# p1-001.net
KiCad netlist of a schematic drawn in EAGLE
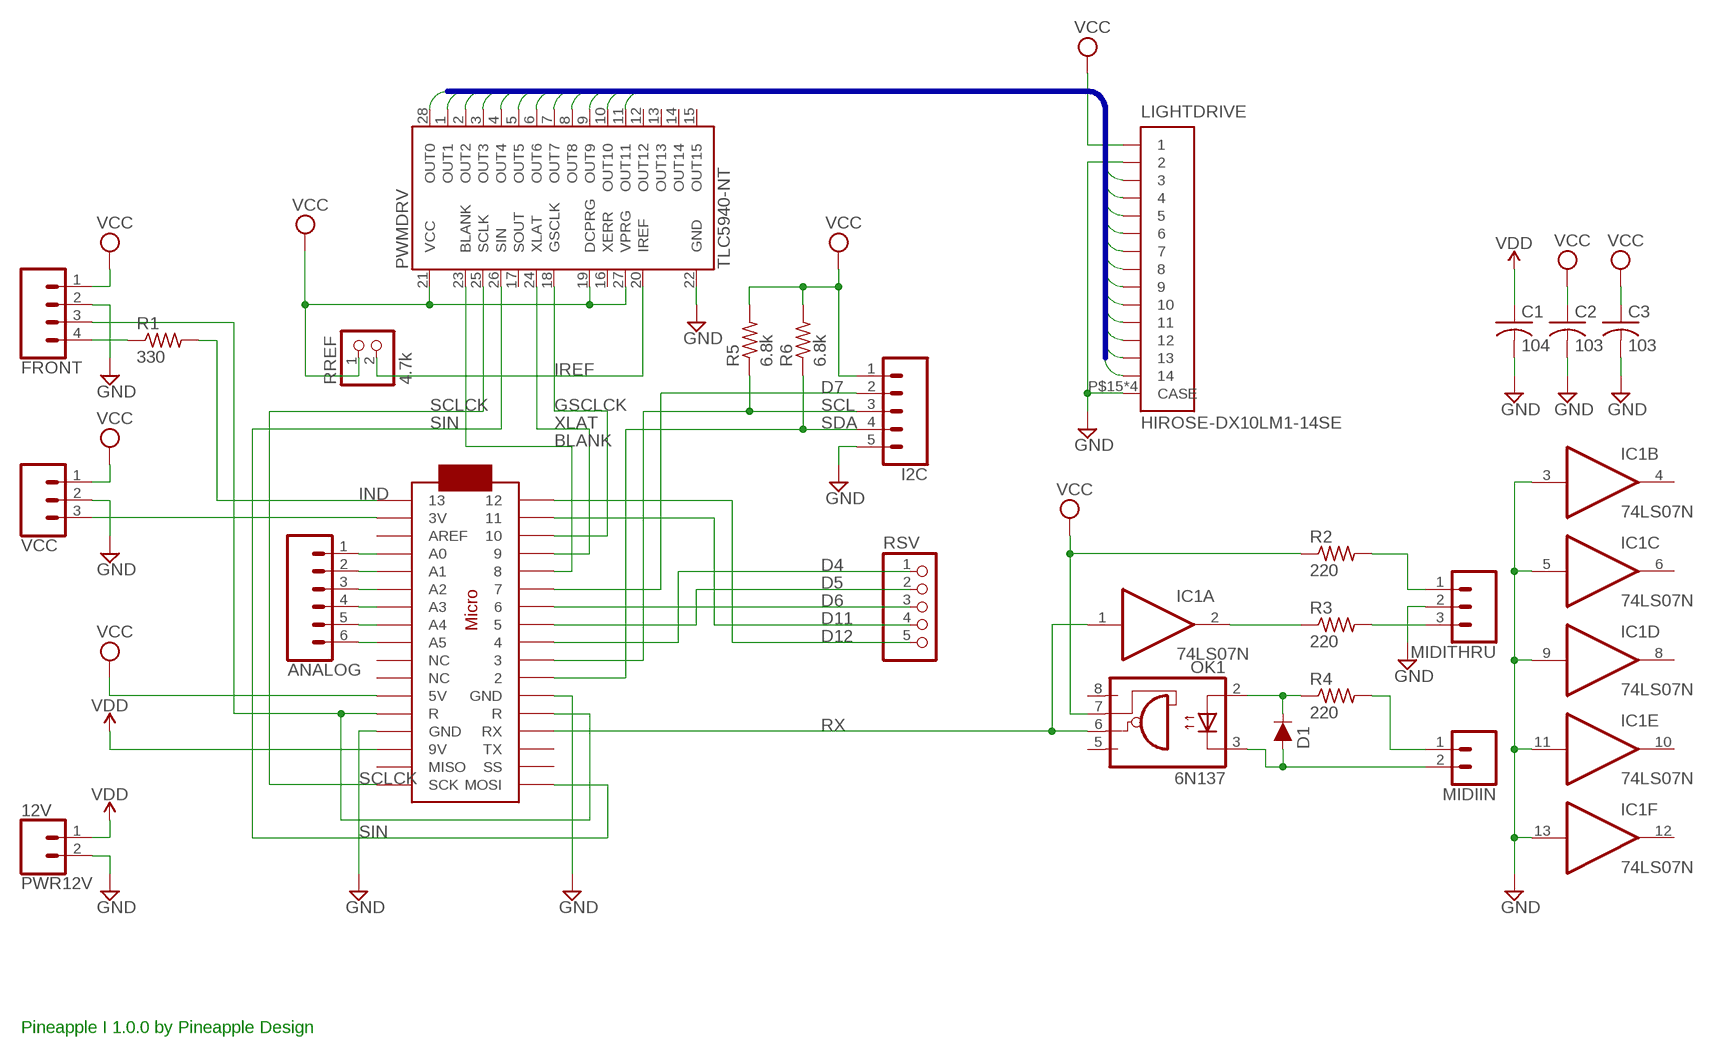
[diagram p0: schematic, sheet 1]

(export (version "E")
  (design (tool "Eeschema 10.0.6"))
  (components
    (comp (ref "ANALOG")
      (value "CONN_061.27MM")
      (footprint "eagle-import:1X06_1.27MM")
      (libsource (lib "eagle-import") (part "CONN_061.27MM"))
    )
    (comp (ref "C1")
      (value "104")
      (footprint "eagle-import:C025-025X050")
      (libsource (lib "eagle-import") (part "C-US025-025X050"))
    )
    (comp (ref "C2")
      (value "103")
      (footprint "eagle-import:C025-025X050")
      (libsource (lib "eagle-import") (part "C-US025-025X050"))
    )
    (comp (ref "C3")
      (value "103")
      (footprint "eagle-import:C025-025X050")
      (libsource (lib "eagle-import") (part "C-US025-025X050"))
    )
    (comp (ref "D1")
      (value "DIODE-1N4148")
      (footprint "eagle-import:DIODE-1N4148")
      (libsource (lib "eagle-import") (part "DIODE-1N4148"))
    )
    (comp (ref "FRONT")
      (value "CONN_04JST-PTH")
      (footprint "eagle-import:JST-4-PTH")
      (libsource (lib "eagle-import") (part "CONN_04JST-PTH"))
    )
    (comp (ref "I2C")
      (value "CONN_05SMD2")
      (footprint "eagle-import:1X05_1MM_RA")
      (libsource (lib "eagle-import") (part "CONN_05SMD2"))
    )
    (comp (ref "IC1")
      (value "74LS07N")
      (footprint "eagle-import:DIL14")
      (libsource (lib "eagle-import") (part "7407NLS"))
    )
    (comp (ref "LIGHTDRIVE")
      (value "HIROSE-DX10LM1-14SE")
      (footprint "eagle-import:HIROSE-DX10LM1-14SE")
      (fields (field (name "MPN") "AXR30545"))
      (libsource (lib "eagle-import") (part "HIROSE-DX10LM1-14SE"))
    )
    (comp (ref "MIDIIN")
      (value "CONN_02JST-PTH-2")
      (footprint "eagle-import:JST-2-PTH")
      (libsource (lib "eagle-import") (part "CONN_02JST-PTH-2"))
    )
    (comp (ref "MIDITHRU")
      (value "CONN_03JST-PTH")
      (footprint "eagle-import:JST-3-PTH")
      (libsource (lib "eagle-import") (part "CONN_03JST-PTH"))
    )
    (comp (ref "OK1")
      (value "6N137")
      (footprint "eagle-import:DIL08")
      (libsource (lib "eagle-import") (part "6N137"))
    )
    (comp (ref "PWMDRV")
      (value "TLC5940-NT")
      (footprint "eagle-import:DIL28-3")
      (libsource (lib "eagle-import") (part "TLC5940-NT"))
    )
    (comp (ref "PWR12V")
      (value "12V")
      (footprint "eagle-import:JST-2-PTH")
      (libsource (lib "eagle-import") (part "CONN_02JST-PTH-2"))
    )
    (comp (ref "R1")
      (value "330")
      (footprint "eagle-import:0204_5")
      (libsource (lib "eagle-import") (part "R-US_0204/5"))
    )
    (comp (ref "R2")
      (value "220")
      (footprint "eagle-import:0204_5")
      (libsource (lib "eagle-import") (part "R-US_0204/5"))
    )
    (comp (ref "R3")
      (value "220")
      (footprint "eagle-import:0204_5")
      (libsource (lib "eagle-import") (part "R-US_0204/5"))
    )
    (comp (ref "R4")
      (value "220")
      (footprint "eagle-import:0204_5")
      (libsource (lib "eagle-import") (part "R-US_0204/5"))
    )
    (comp (ref "R5")
      (value "6.8k")
      (footprint "eagle-import:0204_5")
      (libsource (lib "eagle-import") (part "R-US_0204/5"))
    )
    (comp (ref "R6")
      (value "6.8k")
      (footprint "eagle-import:0204_5")
      (libsource (lib "eagle-import") (part "R-US_0204/5"))
    )
    (comp (ref "RREF")
      (value "4.7k")
      (footprint "eagle-import:1X02")
      (libsource (lib "eagle-import") (part "PINHD-1X2"))
    )
    (comp (ref "RSV")
      (value "PINHD-1X5")
      (footprint "eagle-import:1X05")
      (libsource (lib "eagle-import") (part "PINHD-1X5"))
    )
    (comp (ref "U$1")
      (value "ARDUINOMICRO")
      (footprint "eagle-import:ARDUINOMICRO")
      (libsource (lib "eagle-import") (part "ARDUINOMICRO"))
    )
    (comp (ref "VCC")
      (value "CONN_03JST-PTH")
      (footprint "eagle-import:JST-3-PTH")
      (libsource (lib "eagle-import") (part "SparkFun-Connectors_513_CONN_03JST-PTH"))
    )
  )
  (nets
    (net (code "1") (name "/BLANK") (class "Default")
      (node (ref "PWMDRV") (pin "23") (pinfunction "BLANK_23") (pintype "bidirectional"))
      (node (ref "U$1") (pin "P$5") (pinfunction "8_P$5") (pintype "bidirectional"))
    )
    (net (code "2") (name "/D4") (class "Default")
      (node (ref "RSV") (pin "1") (pinfunction "1_1") (pintype "passive"))
      (node (ref "U$1") (pin "P$9") (pinfunction "4_P$9") (pintype "bidirectional"))
    )
    (net (code "3") (name "/D5") (class "Default")
      (node (ref "RSV") (pin "2") (pinfunction "2_2") (pintype "passive"))
      (node (ref "U$1") (pin "P$8") (pinfunction "5_P$8") (pintype "bidirectional"))
    )
    (net (code "4") (name "/D6") (class "Default")
      (node (ref "RSV") (pin "3") (pinfunction "3_3") (pintype "passive"))
      (node (ref "U$1") (pin "P$7") (pinfunction "6_P$7") (pintype "bidirectional"))
    )
    (net (code "5") (name "/D7") (class "Default")
      (node (ref "I2C") (pin "2") (pinfunction "2_2") (pintype "passive"))
      (node (ref "U$1") (pin "P$6") (pinfunction "7_P$6") (pintype "bidirectional"))
    )
    (net (code "6") (name "/D11") (class "Default")
      (node (ref "RSV") (pin "4") (pinfunction "4_4") (pintype "passive"))
      (node (ref "U$1") (pin "P$2") (pinfunction "11_P$2") (pintype "bidirectional"))
    )
    (net (code "7") (name "/D12") (class "Default")
      (node (ref "RSV") (pin "5") (pinfunction "5_5") (pintype "passive"))
      (node (ref "U$1") (pin "P$1") (pinfunction "12_P$1") (pintype "bidirectional"))
    )
    (net (code "8") (name "/GSCLCK") (class "Default")
      (node (ref "PWMDRV") (pin "18") (pinfunction "GSCLK_18") (pintype "bidirectional"))
      (node (ref "U$1") (pin "P$3") (pinfunction "10_P$3") (pintype "bidirectional"))
    )
    (net (code "9") (name "/IND") (class "Default")
      (node (ref "R1") (pin "2") (pinfunction "2_2") (pintype "passive"))
      (node (ref "U$1") (pin "P$34") (pinfunction "13_P$34") (pintype "bidirectional"))
    )
    (net (code "10") (name "/IREF") (class "Default")
      (node (ref "PWMDRV") (pin "20") (pinfunction "IREF_20") (pintype "bidirectional"))
      (node (ref "RREF") (pin "2") (pinfunction "2_2") (pintype "passive"))
    )
    (net (code "11") (name "/LD1") (class "Default")
      (node (ref "LIGHTDRIVE") (pin "P$3") (pinfunction "3_P$3") (pintype "bidirectional"))
      (node (ref "PWMDRV") (pin "28") (pinfunction "OUT0_28") (pintype "bidirectional"))
    )
    (net (code "12") (name "/LD2") (class "Default")
      (node (ref "LIGHTDRIVE") (pin "P$4") (pinfunction "4_P$4") (pintype "bidirectional"))
      (node (ref "PWMDRV") (pin "1") (pinfunction "OUT1_1") (pintype "bidirectional"))
    )
    (net (code "13") (name "/LD3") (class "Default")
      (node (ref "LIGHTDRIVE") (pin "P$5") (pinfunction "5_P$5") (pintype "bidirectional"))
      (node (ref "PWMDRV") (pin "2") (pinfunction "OUT2_2") (pintype "bidirectional"))
    )
    (net (code "14") (name "/LD4") (class "Default")
      (node (ref "LIGHTDRIVE") (pin "P$6") (pinfunction "6_P$6") (pintype "bidirectional"))
      (node (ref "PWMDRV") (pin "3") (pinfunction "OUT3_3") (pintype "bidirectional"))
    )
    (net (code "15") (name "/LD5") (class "Default")
      (node (ref "LIGHTDRIVE") (pin "P$7") (pinfunction "7_P$7") (pintype "bidirectional"))
      (node (ref "PWMDRV") (pin "4") (pinfunction "OUT4_4") (pintype "bidirectional"))
    )
    (net (code "16") (name "/LD6") (class "Default")
      (node (ref "LIGHTDRIVE") (pin "P$8") (pinfunction "8_P$8") (pintype "bidirectional"))
      (node (ref "PWMDRV") (pin "5") (pinfunction "OUT5_5") (pintype "bidirectional"))
    )
    (net (code "17") (name "/LD7") (class "Default")
      (node (ref "LIGHTDRIVE") (pin "P$9") (pinfunction "9_P$9") (pintype "bidirectional"))
      (node (ref "PWMDRV") (pin "6") (pinfunction "OUT6_6") (pintype "bidirectional"))
    )
    (net (code "18") (name "/LD8") (class "Default")
      (node (ref "LIGHTDRIVE") (pin "P$10") (pinfunction "10_P$10") (pintype "bidirectional"))
      (node (ref "PWMDRV") (pin "7") (pinfunction "OUT7_7") (pintype "bidirectional"))
    )
    (net (code "19") (name "/LD9") (class "Default")
      (node (ref "LIGHTDRIVE") (pin "P$11") (pinfunction "11_P$11") (pintype "bidirectional"))
      (node (ref "PWMDRV") (pin "8") (pinfunction "OUT8_8") (pintype "bidirectional"))
    )
    (net (code "20") (name "/LD10") (class "Default")
      (node (ref "LIGHTDRIVE") (pin "P$12") (pinfunction "12_P$12") (pintype "bidirectional"))
      (node (ref "PWMDRV") (pin "9") (pinfunction "OUT9_9") (pintype "bidirectional"))
    )
    (net (code "21") (name "/LD11") (class "Default")
      (node (ref "LIGHTDRIVE") (pin "P$13") (pinfunction "13_P$13") (pintype "bidirectional"))
      (node (ref "PWMDRV") (pin "10") (pinfunction "OUT10_10") (pintype "bidirectional"))
    )
    (net (code "22") (name "/LD12") (class "Default")
      (node (ref "LIGHTDRIVE") (pin "P$14") (pinfunction "14_P$14") (pintype "bidirectional"))
      (node (ref "PWMDRV") (pin "11") (pinfunction "OUT11_11") (pintype "bidirectional"))
    )
    (net (code "23") (name "/RX") (class "Default")
      (node (ref "IC1") (pin "1") (pinfunction "I_1") (pintype "input"))
      (node (ref "OK1") (pin "6") (pinfunction "VO_6") (pintype "passive"))
      (node (ref "U$1") (pin "P$14") (pinfunction "RX_P$14") (pintype "bidirectional"))
    )
    (net (code "24") (name "/SCL") (class "Default")
      (node (ref "I2C") (pin "3") (pinfunction "3_3") (pintype "passive"))
      (node (ref "R5") (pin "1") (pinfunction "1_1") (pintype "passive"))
      (node (ref "U$1") (pin "P$10") (pinfunction "3_P$10") (pintype "bidirectional"))
    )
    (net (code "25") (name "/SCLCK") (class "Default")
      (node (ref "PWMDRV") (pin "25") (pinfunction "SCLK_25") (pintype "bidirectional"))
      (node (ref "U$1") (pin "P$18") (pinfunction "SCK_P$18") (pintype "bidirectional"))
    )
    (net (code "26") (name "/SDA") (class "Default")
      (node (ref "I2C") (pin "4") (pinfunction "4_4") (pintype "passive"))
      (node (ref "R6") (pin "1") (pinfunction "1_1") (pintype "passive"))
      (node (ref "U$1") (pin "P$11") (pinfunction "2_P$11") (pintype "bidirectional"))
    )
    (net (code "27") (name "/SIN") (class "Default")
      (node (ref "PWMDRV") (pin "26") (pinfunction "SIN_26") (pintype "bidirectional"))
      (node (ref "U$1") (pin "P$17") (pinfunction "MOSI_P$17") (pintype "bidirectional"))
    )
    (net (code "28") (name "/XLAT") (class "Default")
      (node (ref "PWMDRV") (pin "24") (pinfunction "XLAT_24") (pintype "bidirectional"))
      (node (ref "U$1") (pin "P$4") (pinfunction "9_P$4") (pintype "bidirectional"))
    )
    (net (code "29") (name "GND") (class "Default")
      (node (ref "C1") (pin "2") (pinfunction "2_2") (pintype "passive"))
      (node (ref "C2") (pin "2") (pinfunction "2_2") (pintype "passive"))
      (node (ref "C3") (pin "2") (pinfunction "2_2") (pintype "passive"))
      (node (ref "FRONT") (pin "2") (pinfunction "2_2") (pintype "passive"))
      (node (ref "I2C") (pin "5") (pinfunction "5_5") (pintype "passive"))
      (node (ref "IC1") (pin "11") (pinfunction "I_11") (pintype "input"))
      (node (ref "IC1") (pin "13") (pinfunction "I_13") (pintype "input"))
      (node (ref "IC1") (pin "3") (pinfunction "I_3") (pintype "input"))
      (node (ref "IC1") (pin "5") (pinfunction "I_5") (pintype "input"))
      (node (ref "IC1") (pin "9") (pinfunction "I_9") (pintype "input"))
      (node (ref "LIGHTDRIVE") (pin "P$15") (pinfunction "CASE_P$15") (pintype "bidirectional"))
      (node (ref "LIGHTDRIVE") (pin "P$16") (pinfunction "CASE_P$16") (pintype "bidirectional"))
      (node (ref "LIGHTDRIVE") (pin "P$17") (pinfunction "CASE_P$17") (pintype "bidirectional"))
      (node (ref "LIGHTDRIVE") (pin "P$18") (pinfunction "CASE_P$18") (pintype "bidirectional"))
      (node (ref "LIGHTDRIVE") (pin "P$2") (pinfunction "2_P$2") (pintype "bidirectional"))
      (node (ref "MIDITHRU") (pin "2") (pinfunction "2_2") (pintype "passive"))
      (node (ref "PWMDRV") (pin "22") (pinfunction "GND_22") (pintype "bidirectional"))
      (node (ref "PWR12V") (pin "2") (pinfunction "2_2") (pintype "passive"))
      (node (ref "U$1") (pin "P$12") (pinfunction "GND_P$12") (pintype "bidirectional"))
      (node (ref "U$1") (pin "P$21") (pinfunction "GND_P$21") (pintype "bidirectional"))
      (node (ref "VCC") (pin "2") (pinfunction "2_2") (pintype "passive"))
    )
    (net (code "30") (name "Net-(FRONT-Pad3)") (class "Default")
      (node (ref "FRONT") (pin "3") (pinfunction "3_3") (pintype "passive"))
      (node (ref "U$1") (pin "P$13") (pinfunction "R_P$13") (pintype "bidirectional"))
      (node (ref "U$1") (pin "P$22") (pinfunction "R_P$22") (pintype "bidirectional"))
    )
    (net (code "31") (name "Net-(FRONT-Pad4)") (class "Default")
      (node (ref "FRONT") (pin "4") (pinfunction "4_4") (pintype "passive"))
      (node (ref "R1") (pin "1") (pinfunction "1_1") (pintype "passive"))
    )
    (net (code "32") (name "Net-(IC1A-O)") (class "Default")
      (node (ref "IC1") (pin "2") (pinfunction "O_2") (pintype "open_collector"))
      (node (ref "R3") (pin "1") (pinfunction "1_1") (pintype "passive"))
    )
    (net (code "33") (name "Net-(MIDIIN-Pad1)") (class "Default")
      (node (ref "MIDIIN") (pin "1") (pinfunction "1_1") (pintype "passive"))
      (node (ref "R4") (pin "2") (pinfunction "2_2") (pintype "passive"))
    )
    (net (code "34") (name "Net-(MIDITHRU-Pad1)") (class "Default")
      (node (ref "MIDITHRU") (pin "1") (pinfunction "1_1") (pintype "passive"))
      (node (ref "R2") (pin "2") (pinfunction "2_2") (pintype "passive"))
    )
    (net (code "35") (name "Net-(MIDITHRU-Pad3)") (class "Default")
      (node (ref "MIDITHRU") (pin "3") (pinfunction "3_3") (pintype "passive"))
      (node (ref "R3") (pin "2") (pinfunction "2_2") (pintype "passive"))
    )
    (net (code "36") (name "Net-(OK1-A)") (class "Default")
      (node (ref "D1") (pin "C") (pinfunction "C_C") (pintype "passive"))
      (node (ref "OK1") (pin "2") (pinfunction "A_2") (pintype "passive"))
      (node (ref "R4") (pin "1") (pinfunction "1_1") (pintype "passive"))
    )
    (net (code "37") (name "Net-(OK1-C)") (class "Default")
      (node (ref "D1") (pin "A") (pinfunction "A_A") (pintype "passive"))
      (node (ref "MIDIIN") (pin "2") (pinfunction "2_2") (pintype "passive"))
      (node (ref "OK1") (pin "3") (pinfunction "C_3") (pintype "passive"))
    )
    (net (code "38") (name "Net-(U$1-3V)") (class "Default")
      (node (ref "U$1") (pin "P$33") (pinfunction "3V_P$33") (pintype "bidirectional"))
      (node (ref "VCC") (pin "3") (pinfunction "3_3") (pintype "passive"))
    )
    (net (code "39") (name "Net-(U$1-A0)") (class "Default")
      (node (ref "ANALOG") (pin "1") (pinfunction "1_1") (pintype "passive"))
      (node (ref "U$1") (pin "P$31") (pinfunction "A0_P$31") (pintype "bidirectional"))
    )
    (net (code "40") (name "Net-(U$1-A1)") (class "Default")
      (node (ref "ANALOG") (pin "2") (pinfunction "2_2") (pintype "passive"))
      (node (ref "U$1") (pin "P$30") (pinfunction "A1_P$30") (pintype "bidirectional"))
    )
    (net (code "41") (name "Net-(U$1-A2)") (class "Default")
      (node (ref "ANALOG") (pin "3") (pinfunction "3_3") (pintype "passive"))
      (node (ref "U$1") (pin "P$29") (pinfunction "A2_P$29") (pintype "bidirectional"))
    )
    (net (code "42") (name "Net-(U$1-A3)") (class "Default")
      (node (ref "ANALOG") (pin "4") (pinfunction "4_4") (pintype "passive"))
      (node (ref "U$1") (pin "P$28") (pinfunction "A3_P$28") (pintype "bidirectional"))
    )
    (net (code "43") (name "Net-(U$1-A4)") (class "Default")
      (node (ref "ANALOG") (pin "5") (pinfunction "5_5") (pintype "passive"))
      (node (ref "U$1") (pin "P$27") (pinfunction "A4_P$27") (pintype "bidirectional"))
    )
    (net (code "44") (name "Net-(U$1-A5)") (class "Default")
      (node (ref "ANALOG") (pin "6") (pinfunction "6_6") (pintype "passive"))
      (node (ref "U$1") (pin "P$26") (pinfunction "A5_P$26") (pintype "bidirectional"))
    )
    (net (code "45") (name "VCC") (class "Default")
      (node (ref "C2") (pin "1") (pinfunction "1_1") (pintype "passive"))
      (node (ref "C3") (pin "1") (pinfunction "1_1") (pintype "passive"))
      (node (ref "FRONT") (pin "1") (pinfunction "1_1") (pintype "passive"))
      (node (ref "I2C") (pin "1") (pinfunction "1_1") (pintype "passive"))
      (node (ref "LIGHTDRIVE") (pin "P$1") (pinfunction "1_P$1") (pintype "bidirectional"))
      (node (ref "OK1") (pin "7") (pinfunction "VE_7") (pintype "passive"))
      (node (ref "PWMDRV") (pin "19") (pinfunction "DCPRG_19") (pintype "bidirectional"))
      (node (ref "PWMDRV") (pin "21") (pinfunction "VCC_21") (pintype "bidirectional"))
      (node (ref "PWMDRV") (pin "27") (pinfunction "VPRG_27") (pintype "bidirectional"))
      (node (ref "R2") (pin "1") (pinfunction "1_1") (pintype "passive"))
      (node (ref "R5") (pin "2") (pinfunction "2_2") (pintype "passive"))
      (node (ref "R6") (pin "2") (pinfunction "2_2") (pintype "passive"))
      (node (ref "RREF") (pin "1") (pinfunction "1_1") (pintype "passive"))
      (node (ref "U$1") (pin "P$23") (pinfunction "5V_P$23") (pintype "bidirectional"))
      (node (ref "VCC") (pin "1") (pinfunction "1_1") (pintype "passive"))
    )
    (net (code "46") (name "VDD") (class "Default")
      (node (ref "C1") (pin "1") (pinfunction "1_1") (pintype "passive"))
      (node (ref "PWR12V") (pin "1") (pinfunction "1_1") (pintype "passive"))
      (node (ref "U$1") (pin "P$20") (pinfunction "9V_P$20") (pintype "bidirectional"))
    )
    (net (code "47") (name "unconnected-(IC1B-O-Pad4)") (class "Default")
      (node (ref "IC1") (pin "4") (pinfunction "O_4") (pintype "open_collector"))
    )
    (net (code "48") (name "unconnected-(IC1C-O-Pad6)") (class "Default")
      (node (ref "IC1") (pin "6") (pinfunction "O_6") (pintype "open_collector"))
    )
    (net (code "49") (name "unconnected-(IC1D-O-Pad8)") (class "Default")
      (node (ref "IC1") (pin "8") (pinfunction "O_8") (pintype "open_collector"))
    )
    (net (code "50") (name "unconnected-(IC1E-O-Pad10)") (class "Default")
      (node (ref "IC1") (pin "10") (pinfunction "O_10") (pintype "open_collector"))
    )
    (net (code "51") (name "unconnected-(IC1F-O-Pad12)") (class "Default")
      (node (ref "IC1") (pin "12") (pinfunction "O_12") (pintype "open_collector"))
    )
    (net (code "52") (name "unconnected-(OK1-GND-Pad5)") (class "Default")
      (node (ref "OK1") (pin "5") (pinfunction "GND_5") (pintype "passive"))
    )
    (net (code "53") (name "unconnected-(OK1-VCC-Pad8)") (class "Default")
      (node (ref "OK1") (pin "8") (pinfunction "VCC_8") (pintype "passive"))
    )
    (net (code "54") (name "unconnected-(PWMDRV-OUT12-Pad12)") (class "Default")
      (node (ref "PWMDRV") (pin "12") (pinfunction "OUT12_12") (pintype "bidirectional"))
    )
    (net (code "55") (name "unconnected-(PWMDRV-OUT13-Pad13)") (class "Default")
      (node (ref "PWMDRV") (pin "13") (pinfunction "OUT13_13") (pintype "bidirectional"))
    )
    (net (code "56") (name "unconnected-(PWMDRV-OUT14-Pad14)") (class "Default")
      (node (ref "PWMDRV") (pin "14") (pinfunction "OUT14_14") (pintype "bidirectional"))
    )
    (net (code "57") (name "unconnected-(PWMDRV-OUT15-Pad15)") (class "Default")
      (node (ref "PWMDRV") (pin "15") (pinfunction "OUT15_15") (pintype "bidirectional"))
    )
    (net (code "58") (name "unconnected-(PWMDRV-SOUT-Pad17)") (class "Default")
      (node (ref "PWMDRV") (pin "17") (pinfunction "SOUT_17") (pintype "bidirectional"))
    )
    (net (code "59") (name "unconnected-(PWMDRV-XERR-Pad16)") (class "Default")
      (node (ref "PWMDRV") (pin "16") (pinfunction "XERR_16") (pintype "bidirectional"))
    )
    (net (code "60") (name "unconnected-(U$1-AREF-PadP$32)") (class "Default")
      (node (ref "U$1") (pin "P$32") (pinfunction "AREF_P$32") (pintype "bidirectional"))
    )
    (net (code "61") (name "unconnected-(U$1-MISO-PadP$19)") (class "Default")
      (node (ref "U$1") (pin "P$19") (pinfunction "MISO_P$19") (pintype "bidirectional"))
    )
    (net (code "62") (name "unconnected-(U$1-NC-PadP$24)") (class "Default")
      (node (ref "U$1") (pin "P$24") (pinfunction "NC_P$24") (pintype "bidirectional"))
    )
    (net (code "63") (name "unconnected-(U$1-NC-PadP$25)") (class "Default")
      (node (ref "U$1") (pin "P$25") (pinfunction "NC_P$25") (pintype "bidirectional"))
    )
    (net (code "64") (name "unconnected-(U$1-SS-PadP$16)") (class "Default")
      (node (ref "U$1") (pin "P$16") (pinfunction "SS_P$16") (pintype "bidirectional"))
    )
    (net (code "65") (name "unconnected-(U$1-TX-PadP$15)") (class "Default")
      (node (ref "U$1") (pin "P$15") (pinfunction "TX_P$15") (pintype "bidirectional"))
    )
  )
)
